# Main_line_in.net
KiCad netlist of a schematic drawn in Altium Designer
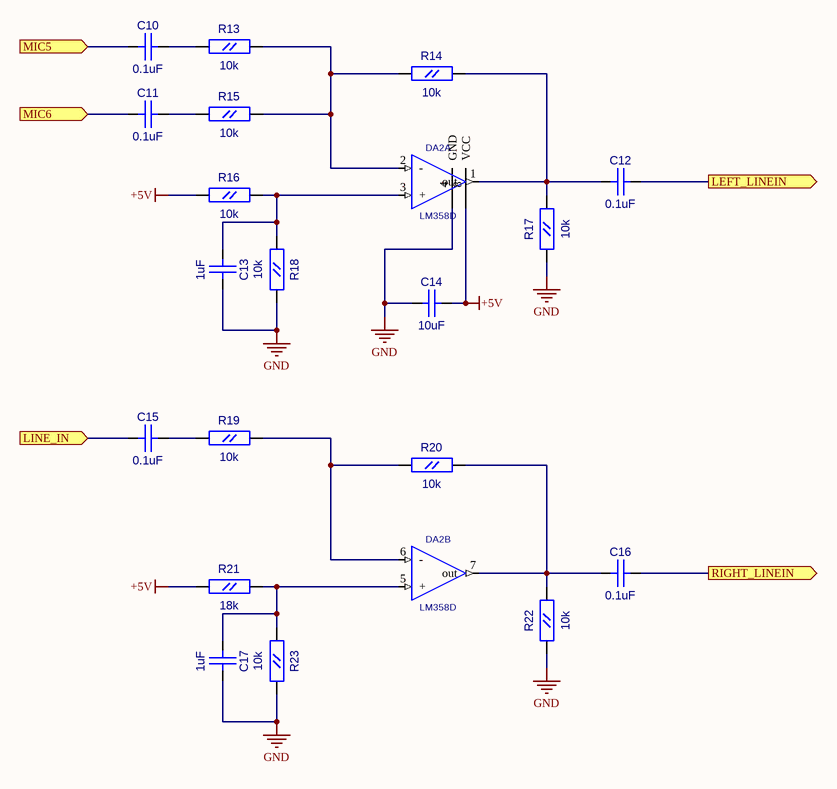
[diagram p0: Main_line_in.SchDoc]

(export (version "E")
  (design (tool "Eeschema 10.0.6"))
  (components
    (comp (ref "C10")
      (value "0.1uF")
      (footprint "CC0603")
      (description "CC0603")
      (libsource (lib "gprs_modem_2") (part "CC0603"))
    )
    (comp (ref "C11")
      (value "0.1uF")
      (footprint "CC0603")
      (description "CC0603")
      (libsource (lib "gprs_modem_2") (part "CC0603"))
    )
    (comp (ref "C12")
      (value "0.1uF")
      (footprint "CC0603")
      (description "CC0603")
      (libsource (lib "gprs_modem_2") (part "CC0603"))
    )
    (comp (ref "C13")
      (value "1uF")
      (footprint "CC0603")
      (description "CC0603")
      (libsource (lib "gprs_modem_2") (part "CC0603"))
    )
    (comp (ref "C14")
      (value "10uF")
      (footprint "CC0805")
      (description "CC0805")
      (libsource (lib "gprs_modem_2") (part "CC0805"))
    )
    (comp (ref "C15")
      (value "0.1uF")
      (footprint "CC0603")
      (description "CC0603")
      (libsource (lib "gprs_modem_2") (part "CC0603"))
    )
    (comp (ref "C16")
      (value "0.1uF")
      (footprint "CC0603")
      (description "CC0603")
      (libsource (lib "gprs_modem_2") (part "CC0603"))
    )
    (comp (ref "C17")
      (value "1uF")
      (footprint "CC0603")
      (description "CC0603")
      (libsource (lib "gprs_modem_2") (part "CC0603"))
    )
    (comp (ref "DA2") (value "LM358D") (footprint "SO-8") (libsource (lib "Schetchik") (part "LM358D")))
    (comp (ref "R13")
      (value "10k")
      (footprint "RC0603")
      (description "RC0603")
      (libsource (lib "gprs_modem_2") (part "RC0603"))
    )
    (comp (ref "R14")
      (value "10k")
      (footprint "RC0603")
      (description "RC0603")
      (libsource (lib "gprs_modem_2") (part "RC0603"))
    )
    (comp (ref "R15")
      (value "10k")
      (footprint "RC0603")
      (description "RC0603")
      (libsource (lib "gprs_modem_2") (part "RC0603"))
    )
    (comp (ref "R16")
      (value "10k")
      (footprint "RC0603")
      (description "RC0603")
      (libsource (lib "gprs_modem_2") (part "RC0603"))
    )
    (comp (ref "R17")
      (value "10k")
      (footprint "RC0603")
      (description "RC0603")
      (libsource (lib "gprs_modem_2") (part "RC0603"))
    )
    (comp (ref "R18")
      (value "10k")
      (footprint "RC0603")
      (description "RC0603")
      (libsource (lib "gprs_modem_2") (part "RC0603"))
    )
    (comp (ref "R19")
      (value "10k")
      (footprint "RC0603")
      (description "RC0603")
      (libsource (lib "gprs_modem_2") (part "RC0603"))
    )
    (comp (ref "R20")
      (value "10k")
      (footprint "RC0603")
      (description "RC0603")
      (libsource (lib "gprs_modem_2") (part "RC0603"))
    )
    (comp (ref "R21")
      (value "18k")
      (footprint "RC0603")
      (description "RC0603")
      (libsource (lib "gprs_modem_2") (part "RC0603"))
    )
    (comp (ref "R22")
      (value "10k")
      (footprint "RC0603")
      (description "RC0603")
      (libsource (lib "gprs_modem_2") (part "RC0603"))
    )
    (comp (ref "R23")
      (value "10k")
      (footprint "RC0603")
      (description "RC0603")
      (libsource (lib "gprs_modem_2") (part "RC0603"))
    )
  )
  (nets
    (net (code "1") (name "+5V") (class "Default")
      (node (ref "C14") (pin "2") (pinfunction "B_2") (pintype "passive"))
      (node (ref "DA2") (pin "8") (pinfunction "VCC_8") (pintype "power_in"))
      (node (ref "R16") (pin "1") (pinfunction "A_1") (pintype "passive"))
      (node (ref "R21") (pin "1") (pinfunction "A_1") (pintype "passive"))
    )
    (net (code "2") (name "/LEFT_LINEIN") (class "Default")
      (node (ref "C12") (pin "2") (pinfunction "B_2") (pintype "passive"))
    )
    (net (code "3") (name "/LINE_IN") (class "Default")
      (node (ref "C15") (pin "1") (pinfunction "A_1") (pintype "passive"))
    )
    (net (code "4") (name "/MIC5") (class "Default")
      (node (ref "C10") (pin "1") (pinfunction "A_1") (pintype "passive"))
    )
    (net (code "5") (name "/MIC6") (class "Default")
      (node (ref "C11") (pin "1") (pinfunction "A_1") (pintype "passive"))
    )
    (net (code "6") (name "/RIGHT_LINEIN") (class "Default")
      (node (ref "C16") (pin "2") (pinfunction "B_2") (pintype "passive"))
    )
    (net (code "7") (name "GND") (class "Default")
      (node (ref "C13") (pin "2") (pinfunction "B_2") (pintype "passive"))
      (node (ref "C14") (pin "1") (pinfunction "A_1") (pintype "passive"))
      (node (ref "C17") (pin "2") (pinfunction "B_2") (pintype "passive"))
      (node (ref "DA2") (pin "4") (pinfunction "GND_4") (pintype "power_in"))
      (node (ref "R17") (pin "1") (pinfunction "A_1") (pintype "passive"))
      (node (ref "R18") (pin "2") (pinfunction "B_2") (pintype "passive"))
      (node (ref "R22") (pin "1") (pinfunction "A_1") (pintype "passive"))
      (node (ref "R23") (pin "2") (pinfunction "B_2") (pintype "passive"))
    )
    (net (code "8") (name "Net-(C10-B)") (class "Default")
      (node (ref "C10") (pin "2") (pinfunction "B_2") (pintype "passive"))
      (node (ref "R13") (pin "1") (pinfunction "A_1") (pintype "passive"))
    )
    (net (code "9") (name "Net-(C11-B)") (class "Default")
      (node (ref "C11") (pin "2") (pinfunction "B_2") (pintype "passive"))
      (node (ref "R15") (pin "1") (pinfunction "A_1") (pintype "passive"))
    )
    (net (code "10") (name "Net-(C12-A)") (class "Default")
      (node (ref "C12") (pin "1") (pinfunction "A_1") (pintype "passive"))
      (node (ref "DA2") (pin "1") (pinfunction "out_1") (pintype "output"))
      (node (ref "R14") (pin "2") (pinfunction "B_2") (pintype "passive"))
      (node (ref "R17") (pin "2") (pinfunction "B_2") (pintype "passive"))
    )
    (net (code "11") (name "Net-(C13-A)") (class "Default")
      (node (ref "C13") (pin "1") (pinfunction "A_1") (pintype "passive"))
      (node (ref "DA2") (pin "3") (pinfunction "+_3") (pintype "input"))
      (node (ref "R16") (pin "2") (pinfunction "B_2") (pintype "passive"))
      (node (ref "R18") (pin "1") (pinfunction "A_1") (pintype "passive"))
    )
    (net (code "12") (name "Net-(C15-B)") (class "Default")
      (node (ref "C15") (pin "2") (pinfunction "B_2") (pintype "passive"))
      (node (ref "R19") (pin "1") (pinfunction "A_1") (pintype "passive"))
    )
    (net (code "13") (name "Net-(C16-A)") (class "Default")
      (node (ref "C16") (pin "1") (pinfunction "A_1") (pintype "passive"))
      (node (ref "DA2") (pin "7") (pinfunction "out_7") (pintype "output"))
      (node (ref "R20") (pin "2") (pinfunction "B_2") (pintype "passive"))
      (node (ref "R22") (pin "2") (pinfunction "B_2") (pintype "passive"))
    )
    (net (code "14") (name "Net-(C17-A)") (class "Default")
      (node (ref "C17") (pin "1") (pinfunction "A_1") (pintype "passive"))
      (node (ref "DA2") (pin "5") (pinfunction "+_5") (pintype "input"))
      (node (ref "R21") (pin "2") (pinfunction "B_2") (pintype "passive"))
      (node (ref "R23") (pin "1") (pinfunction "A_1") (pintype "passive"))
    )
    (net (code "15") (name "Net-(DA2A--)") (class "Default")
      (node (ref "DA2") (pin "2") (pinfunction "-_2") (pintype "input"))
      (node (ref "R13") (pin "2") (pinfunction "B_2") (pintype "passive"))
      (node (ref "R14") (pin "1") (pinfunction "A_1") (pintype "passive"))
      (node (ref "R15") (pin "2") (pinfunction "B_2") (pintype "passive"))
    )
    (net (code "16") (name "Net-(DA2B--)") (class "Default")
      (node (ref "DA2") (pin "6") (pinfunction "-_6") (pintype "input"))
      (node (ref "R19") (pin "2") (pinfunction "B_2") (pintype "passive"))
      (node (ref "R20") (pin "1") (pinfunction "A_1") (pintype "passive"))
    )
  )
)
